# 02_IMU.net
KiCad netlist of a schematic drawn in Altium Designer
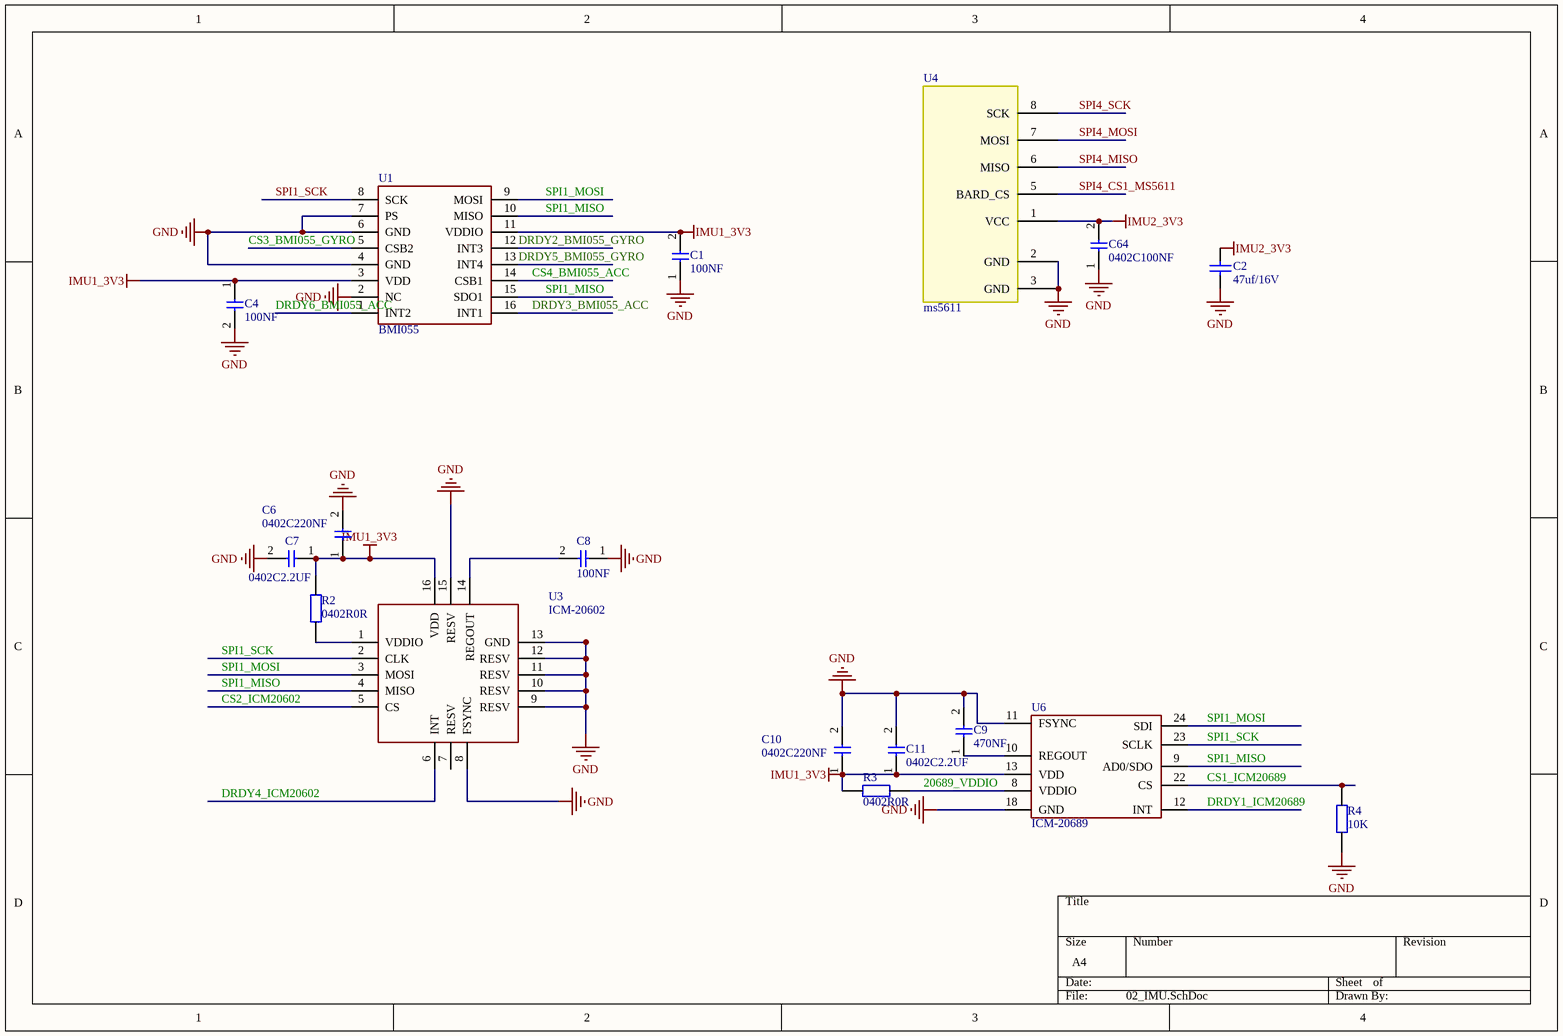
[diagram p0: 02_IMU.SchDoc]

(export (version "E")
  (design (tool "Eeschema 10.0.6"))
  (components
    (comp (ref "C1") (value "100NF") (footprint "0402C") (libsource (lib "CUAV") (part "0402C220NF")))
    (comp (ref "C2")
      (value "47uf/16V")
      (description "Capacitor")
      (libsource (lib "Miscellaneous Devices") (part "Cap"))
    )
    (comp (ref "C4") (value "100NF") (footprint "0402C") (libsource (lib "CUAV") (part "0402C220NF")))
    (comp (ref "C6") (value "0402C220NF") (footprint "0402C") (libsource (lib "CUAV") (part "0402C220NF")))
    (comp (ref "C7") (value "0402C2.2UF") (footprint "0402C") (libsource (lib "CUAV") (part "0402C2.2UF")))
    (comp (ref "C8") (value "100NF") (footprint "0402C") (libsource (lib "CUAV") (part "0402C220NF")))
    (comp (ref "C9") (value "470NF") (footprint "0402C") (libsource (lib "CUAV") (part "0402C2.2UF")))
    (comp (ref "C10") (value "0402C220NF") (footprint "0402C") (libsource (lib "CUAV") (part "0402C220NF")))
    (comp (ref "C11") (value "0402C2.2UF") (footprint "0402C") (libsource (lib "CUAV") (part "0402C2.2UF")))
    (comp (ref "C64")
      (value "0402C100NF")
      (footprint "0402C")
      (description "50V 5%")
      (libsource (lib "CUAV") (part "0402C100NF"))
    )
    (comp (ref "R2")
      (value "0402R0R")
      (footprint "0402R")
      (description "0402R0R 1%")
      (libsource (lib "CUAV") (part "0402R0R"))
    )
    (comp (ref "R3")
      (value "0402R0R")
      (footprint "0402R")
      (description "0402R0R 1%")
      (libsource (lib "") (part "0402R0R_1"))
    )
    (comp (ref "R4")
      (value "10K")
      (footprint "0402R")
      (description "0402R0R 1%")
      (libsource (lib "CUAV") (part "0402R0R"))
    )
    (comp (ref "U1") (value "BMI055") (footprint "LGA16_BMI055") (libsource (lib "CUAV") (part "BMI055")))
    (comp (ref "U3") (value "ICM-20602") (footprint "LGA16") (libsource (lib "CUAV") (part "ICM-20602")))
    (comp (ref "U4") (value "ms5611") (footprint "ms5611") (libsource (lib "hack") (part "ms5611")))
    (comp (ref "U6") (value "ICM-20689") (footprint "QFN24") (libsource (lib "CUAV") (part "ICM-20689")))
  )
  (nets
    (net (code "1") (name "/20689_VDDIO") (class "Default")
      (node (ref "R3") (pin "2") (pintype "passive"))
      (node (ref "U6") (pin "8") (pinfunction "VDDIO_8") (pintype "passive"))
    )
    (net (code "2") (name "/CS1_ICM20689") (class "Default")
      (node (ref "R4") (pin "2") (pintype "passive"))
      (node (ref "U6") (pin "22") (pinfunction "CS_22") (pintype "passive"))
    )
    (net (code "3") (name "/CS2_ICM20602") (class "Default")
      (node (ref "U3") (pin "5") (pinfunction "CS_5") (pintype "passive"))
    )
    (net (code "4") (name "/CS3_BMI055_GYRO") (class "Default")
      (node (ref "U1") (pin "5") (pinfunction "CSB2_5") (pintype "passive"))
    )
    (net (code "5") (name "/CS4_BMI055_ACC") (class "Default")
      (node (ref "U1") (pin "14") (pinfunction "CSB1_14") (pintype "passive"))
    )
    (net (code "6") (name "/DRDY1_ICM20689") (class "Default")
      (node (ref "U6") (pin "12") (pinfunction "INT_12") (pintype "passive"))
    )
    (net (code "7") (name "/DRDY2_BMI055_GYRO") (class "Default")
      (node (ref "U1") (pin "12") (pinfunction "INT3_12") (pintype "passive"))
    )
    (net (code "8") (name "/DRDY3_BMI055_ACC") (class "Default")
      (node (ref "U1") (pin "16") (pinfunction "INT1_16") (pintype "passive"))
    )
    (net (code "9") (name "/DRDY4_ICM20602") (class "Default")
      (node (ref "U3") (pin "6") (pinfunction "INT_6") (pintype "passive"))
    )
    (net (code "10") (name "/DRDY5_BMI055_GYRO") (class "Default")
      (node (ref "U1") (pin "13") (pinfunction "INT4_13") (pintype "passive"))
    )
    (net (code "11") (name "/DRDY6_BMI055_ACC") (class "Default")
      (node (ref "U1") (pin "1") (pinfunction "INT2_1") (pintype "passive"))
    )
    (net (code "12") (name "/SPI1_MISO") (class "Default")
      (node (ref "U1") (pin "10") (pinfunction "MISO_10") (pintype "passive"))
      (node (ref "U1") (pin "15") (pinfunction "SDO1_15") (pintype "passive"))
      (node (ref "U3") (pin "4") (pinfunction "MISO_4") (pintype "passive"))
      (node (ref "U6") (pin "9") (pinfunction "AD0/SDO_9") (pintype "passive"))
    )
    (net (code "13") (name "/SPI1_MOSI") (class "Default")
      (node (ref "U1") (pin "9") (pinfunction "MOSI_9") (pintype "passive"))
      (node (ref "U3") (pin "3") (pinfunction "MOSI_3") (pintype "passive"))
      (node (ref "U6") (pin "24") (pinfunction "SDI_24") (pintype "passive"))
    )
    (net (code "14") (name "/SPI1_SCK") (class "Default")
      (node (ref "U1") (pin "8") (pinfunction "SCK_8") (pintype "passive"))
      (node (ref "U3") (pin "2") (pinfunction "CLK_2") (pintype "passive"))
      (node (ref "U6") (pin "23") (pinfunction "SCLK_23") (pintype "passive"))
    )
    (net (code "15") (name "/SPI4_CS1_MS5611") (class "Default")
      (node (ref "U4") (pin "5") (pinfunction "BARD_CS_5") (pintype "passive"))
    )
    (net (code "16") (name "/SPI4_MISO") (class "Default")
      (node (ref "U4") (pin "6") (pinfunction "MISO_6") (pintype "passive"))
    )
    (net (code "17") (name "/SPI4_MOSI") (class "Default")
      (node (ref "U4") (pin "7") (pinfunction "MOSI_7") (pintype "passive"))
    )
    (net (code "18") (name "/SPI4_SCK") (class "Default")
      (node (ref "U4") (pin "8") (pinfunction "SCK_8") (pintype "passive"))
    )
    (net (code "19") (name "GND") (class "Default")
      (node (ref "C1") (pin "1") (pintype "passive"))
      (node (ref "C10") (pin "2") (pintype "passive"))
      (node (ref "C11") (pin "2") (pintype "passive"))
      (node (ref "C2") (pin "2") (pinfunction "2_2") (pintype "passive"))
      (node (ref "C4") (pin "2") (pintype "passive"))
      (node (ref "C6") (pin "2") (pintype "passive"))
      (node (ref "C64") (pin "1") (pintype "passive"))
      (node (ref "C7") (pin "2") (pintype "passive"))
      (node (ref "C8") (pin "1") (pintype "passive"))
      (node (ref "C9") (pin "2") (pintype "passive"))
      (node (ref "R4") (pin "1") (pintype "passive"))
      (node (ref "U1") (pin "2") (pinfunction "NC_2") (pintype "passive"))
      (node (ref "U1") (pin "4") (pinfunction "GND_4") (pintype "passive"))
      (node (ref "U1") (pin "6") (pinfunction "GND_6") (pintype "passive"))
      (node (ref "U1") (pin "7") (pinfunction "PS_7") (pintype "passive"))
      (node (ref "U3") (pin "10") (pinfunction "RESV_10") (pintype "passive"))
      (node (ref "U3") (pin "11") (pinfunction "RESV_11") (pintype "passive"))
      (node (ref "U3") (pin "12") (pinfunction "RESV_12") (pintype "passive"))
      (node (ref "U3") (pin "13") (pinfunction "GND_13") (pintype "passive"))
      (node (ref "U3") (pin "15") (pinfunction "RESV_15") (pintype "passive"))
      (node (ref "U3") (pin "8") (pinfunction "FSYNC_8") (pintype "passive"))
      (node (ref "U3") (pin "9") (pinfunction "RESV_9") (pintype "passive"))
      (node (ref "U4") (pin "2") (pinfunction "GND_2") (pintype "passive"))
      (node (ref "U4") (pin "3") (pinfunction "GND_3") (pintype "passive"))
      (node (ref "U6") (pin "11") (pinfunction "FSYNC_11") (pintype "passive"))
      (node (ref "U6") (pin "18") (pinfunction "GND_18") (pintype "passive"))
    )
    (net (code "20") (name "IMU1_3V3") (class "Default")
      (node (ref "C1") (pin "2") (pintype "passive"))
      (node (ref "C10") (pin "1") (pintype "passive"))
      (node (ref "C11") (pin "1") (pintype "passive"))
      (node (ref "C4") (pin "1") (pintype "passive"))
      (node (ref "C6") (pin "1") (pintype "passive"))
      (node (ref "C7") (pin "1") (pintype "passive"))
      (node (ref "R2") (pin "2") (pintype "passive"))
      (node (ref "R3") (pin "1") (pintype "passive"))
      (node (ref "U1") (pin "11") (pinfunction "VDDIO_11") (pintype "passive"))
      (node (ref "U1") (pin "3") (pinfunction "VDD_3") (pintype "passive"))
      (node (ref "U3") (pin "16") (pinfunction "VDD_16") (pintype "passive"))
      (node (ref "U6") (pin "13") (pinfunction "VDD_13") (pintype "passive"))
    )
    (net (code "21") (name "IMU2_3V3") (class "Default")
      (node (ref "C2") (pin "1") (pinfunction "1_1") (pintype "passive"))
      (node (ref "C64") (pin "2") (pintype "passive"))
      (node (ref "U4") (pin "1") (pinfunction "VCC_1") (pintype "passive"))
    )
    (net (code "22") (name "Net-(U3-REGOUT)") (class "Default")
      (node (ref "C8") (pin "2") (pintype "passive"))
      (node (ref "U3") (pin "14") (pinfunction "REGOUT_14") (pintype "passive"))
    )
    (net (code "23") (name "Net-(U3-VDDIO)") (class "Default")
      (node (ref "R2") (pin "1") (pintype "passive"))
      (node (ref "U3") (pin "1") (pinfunction "VDDIO_1") (pintype "passive"))
    )
    (net (code "24") (name "Net-(U6-REGOUT)") (class "Default")
      (node (ref "C9") (pin "1") (pintype "passive"))
      (node (ref "U6") (pin "10") (pinfunction "REGOUT_10") (pintype "passive"))
    )
    (net (code "25") (name "unconnected-(U3-RESV-Pad7)") (class "Default")
      (node (ref "U3") (pin "7") (pinfunction "RESV_7") (pintype "passive"))
    )
  )
)
